# USB_ISOL.net
KiCad netlist of a schematic drawn in Altium Designer
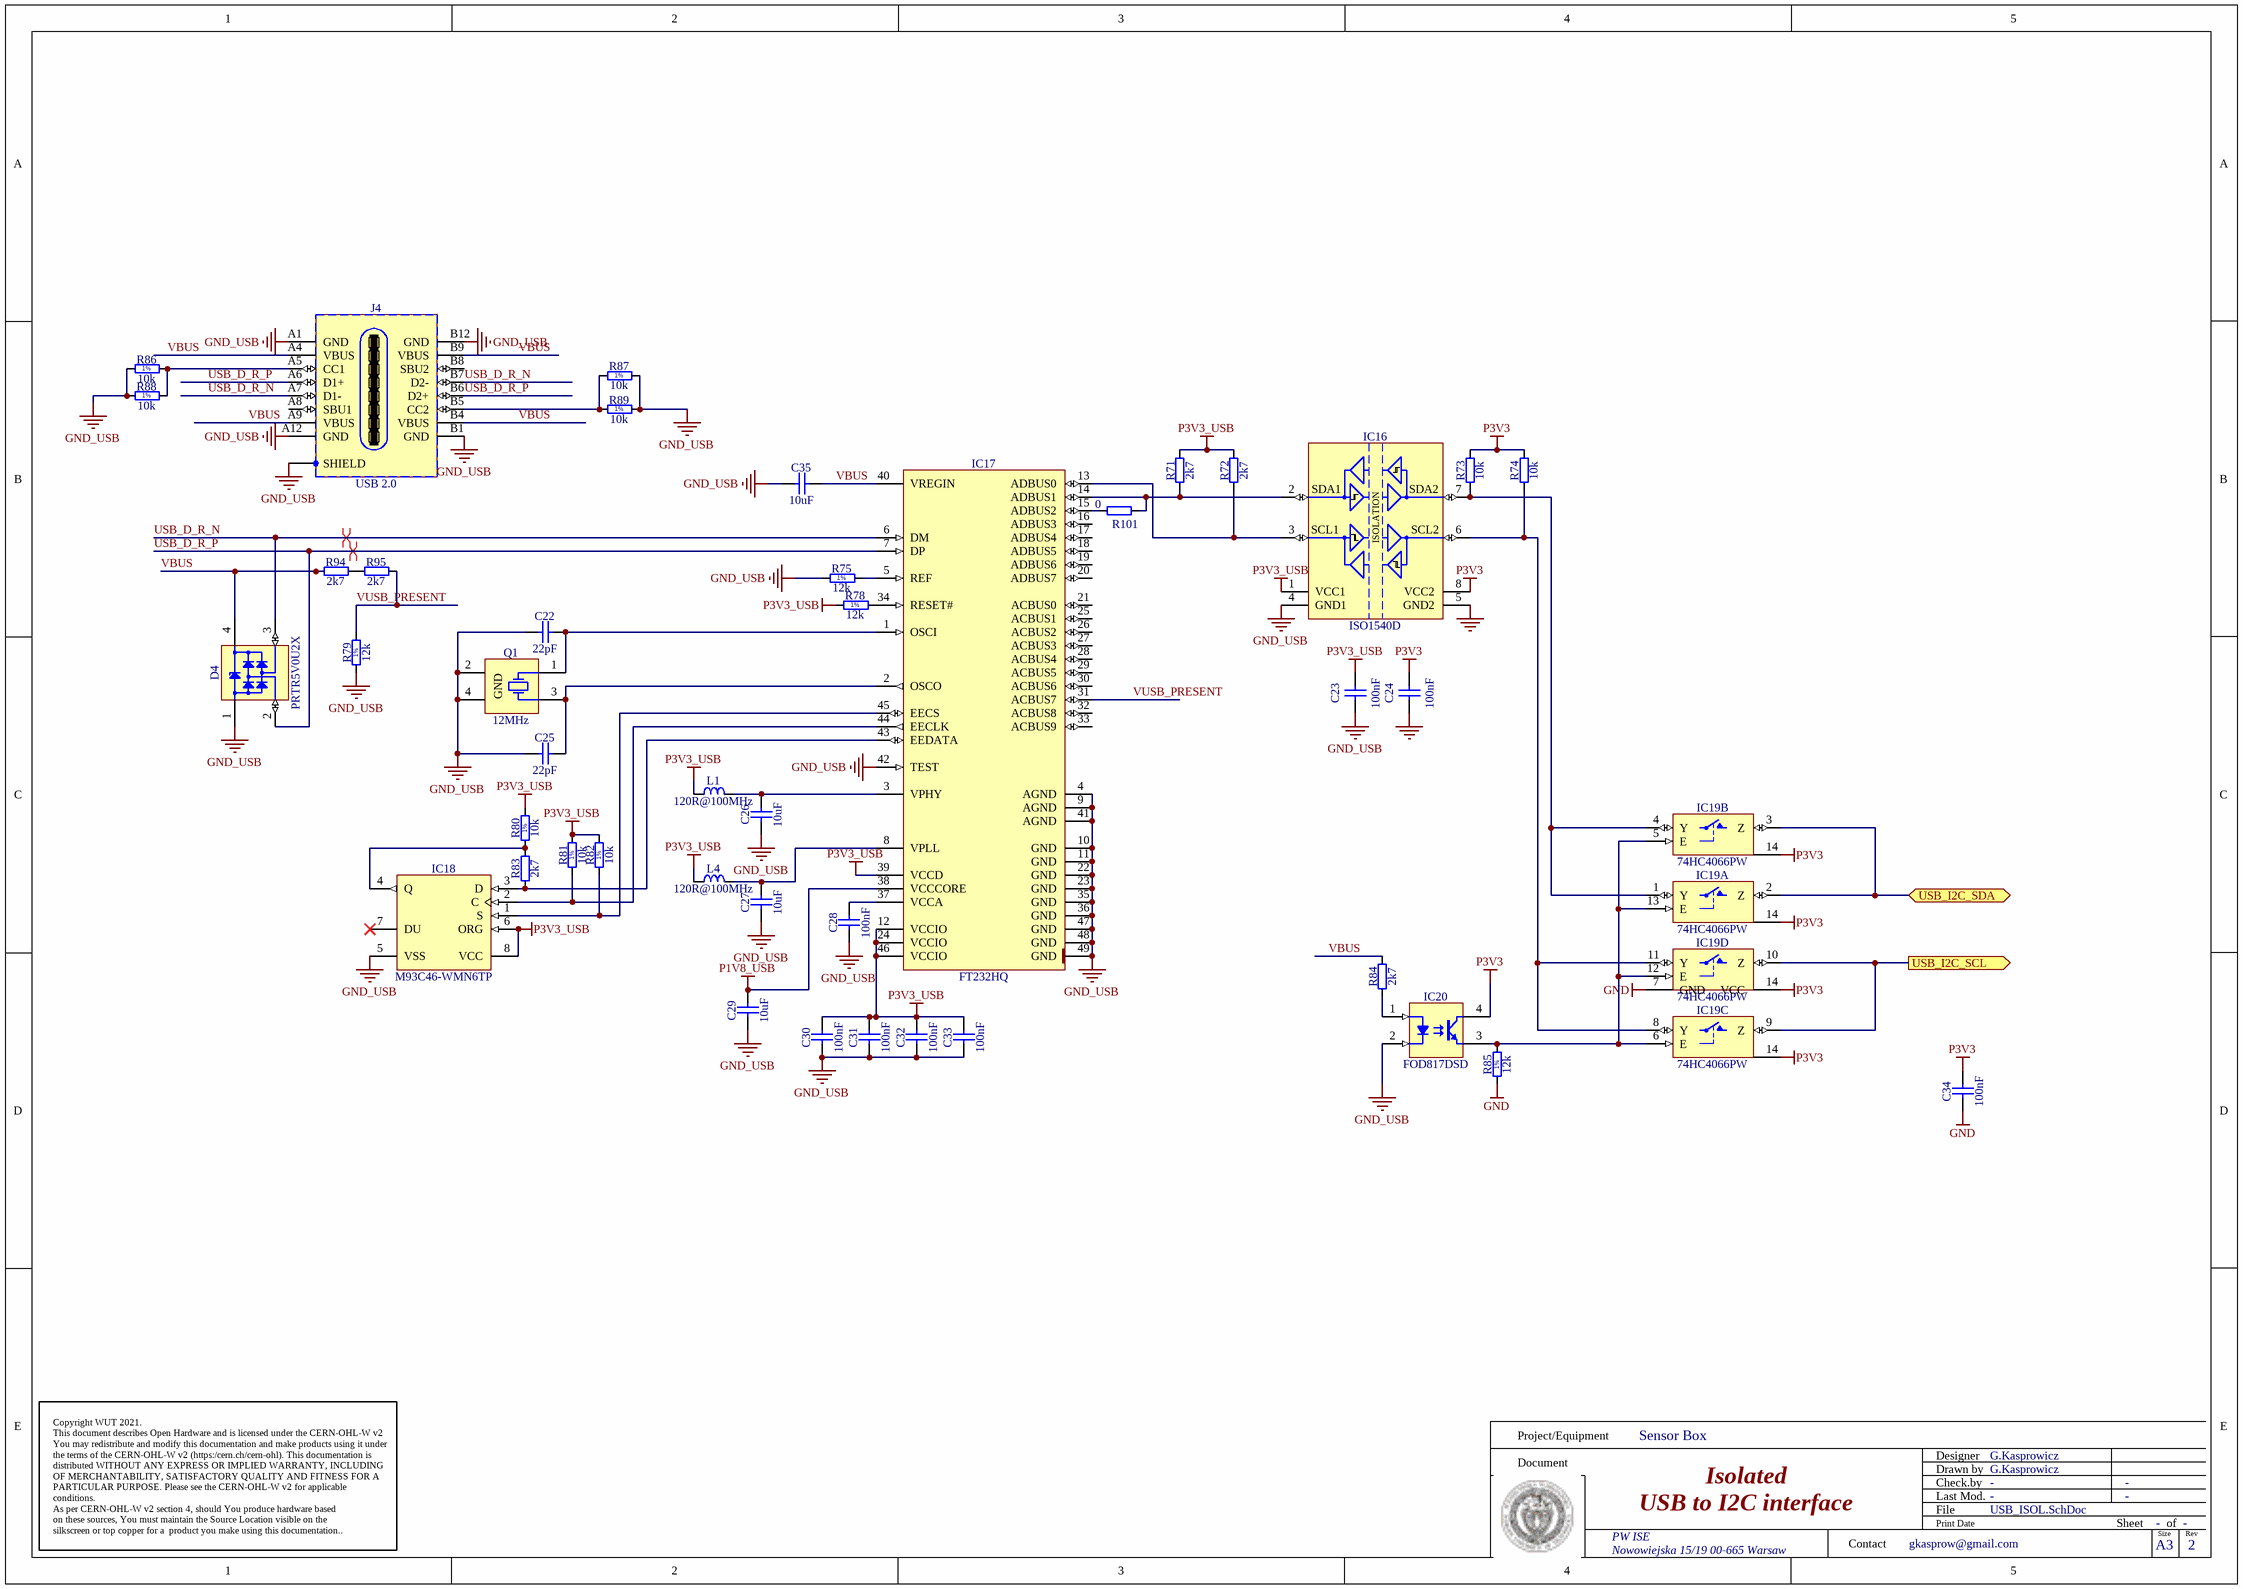
[diagram p0: USB_ISOL.SchDoc]

(export (version "E")
  (design (tool "Eeschema 10.0.6"))
  (components
    (comp (ref "C22")
      (value "22pF")
      (footprint "CAPC1005X55N")
      (description "Non-polarised capacitor")
      (fields
        (field (name "PART NUMBER") "CC0402_22PF_50V_5%_C0G")
        (field (name "VOLTAGE") "50V")
        (field (name "AUTHOR") "CERN DEM JLC")
      )
      (libsource (lib "Capacitors") (part "Capacitor - non polarized"))
    )
    (comp (ref "C23")
      (value "100nF")
      (footprint "CAPC1005X55N")
      (description "Non-polarised capacitor")
      (fields
        (field (name "PART NUMBER") "CC0402_100NF_50V_10%_X7R")
        (field (name "VOLTAGE") "50V")
        (field (name "AUTHOR") "CERN DEM MR")
      )
      (libsource (lib "Capacitors") (part "Capacitor - non polarized"))
    )
    (comp (ref "C24")
      (value "100nF")
      (footprint "CAPC1005X55N")
      (description "Non-polarised capacitor")
      (fields
        (field (name "PART NUMBER") "CC0402_100NF_50V_10%_X7R")
        (field (name "VOLTAGE") "50V")
        (field (name "AUTHOR") "CERN DEM MR")
      )
      (libsource (lib "Capacitors") (part "Capacitor - non polarized"))
    )
    (comp (ref "C25")
      (value "22pF")
      (footprint "CAPC1005X55N")
      (description "Non-polarised capacitor")
      (fields
        (field (name "PART NUMBER") "CC0402_22PF_50V_5%_C0G")
        (field (name "VOLTAGE") "50V")
        (field (name "AUTHOR") "CERN DEM JLC")
      )
      (libsource (lib "Capacitors") (part "Capacitor - non polarized"))
    )
    (comp (ref "C26")
      (value "10uF")
      (footprint "CAPC2012X95N")
      (description "Non-polarised capacitor")
      (fields
        (field (name "PART NUMBER") "CC0805_10UF_25V_10%_X5R")
        (field (name "VOLTAGE") "25V")
        (field (name "AUTHOR") "CERN DEM JLC")
      )
      (libsource (lib "Capacitors") (part "Capacitor - non polarized"))
    )
    (comp (ref "C27")
      (value "10uF")
      (footprint "CAPC2012X95N")
      (description "Non-polarised capacitor")
      (fields
        (field (name "PART NUMBER") "CC0805_10UF_25V_10%_X5R")
        (field (name "VOLTAGE") "25V")
        (field (name "AUTHOR") "CERN DEM JLC")
      )
      (libsource (lib "Capacitors") (part "Capacitor - non polarized"))
    )
    (comp (ref "C28")
      (value "100nF")
      (footprint "CAPC1005X55N")
      (description "Non-polarised capacitor")
      (fields
        (field (name "PART NUMBER") "CC0402_100NF_50V_10%_X7R")
        (field (name "VOLTAGE") "50V")
        (field (name "AUTHOR") "CERN DEM MR")
      )
      (libsource (lib "Capacitors") (part "Capacitor - non polarized"))
    )
    (comp (ref "C29")
      (value "10uF")
      (footprint "CAPC2012X95N")
      (description "Non-polarised capacitor")
      (fields
        (field (name "PART NUMBER") "CC0805_10UF_25V_10%_X5R")
        (field (name "VOLTAGE") "25V")
        (field (name "AUTHOR") "CERN DEM JLC")
      )
      (libsource (lib "Capacitors") (part "Capacitor - non polarized"))
    )
    (comp (ref "C30")
      (value "100nF")
      (footprint "CAPC1005X55N")
      (description "Non-polarised capacitor")
      (fields
        (field (name "PART NUMBER") "CC0402_100NF_50V_10%_X7R")
        (field (name "VOLTAGE") "50V")
        (field (name "AUTHOR") "CERN DEM MR")
      )
      (libsource (lib "Capacitors") (part "Capacitor - non polarized"))
    )
    (comp (ref "C31")
      (value "100nF")
      (footprint "CAPC1005X55N")
      (description "Non-polarised capacitor")
      (fields
        (field (name "PART NUMBER") "CC0402_100NF_50V_10%_X7R")
        (field (name "VOLTAGE") "50V")
        (field (name "AUTHOR") "CERN DEM MR")
      )
      (libsource (lib "Capacitors") (part "Capacitor - non polarized"))
    )
    (comp (ref "C32")
      (value "100nF")
      (footprint "CAPC1005X55N")
      (description "Non-polarised capacitor")
      (fields
        (field (name "PART NUMBER") "CC0402_100NF_50V_10%_X7R")
        (field (name "VOLTAGE") "50V")
        (field (name "AUTHOR") "CERN DEM MR")
      )
      (libsource (lib "Capacitors") (part "Capacitor - non polarized"))
    )
    (comp (ref "C33")
      (value "100nF")
      (footprint "CAPC1005X55N")
      (description "Non-polarised capacitor")
      (fields
        (field (name "PART NUMBER") "CC0402_100NF_50V_10%_X7R")
        (field (name "VOLTAGE") "50V")
        (field (name "AUTHOR") "CERN DEM MR")
      )
      (libsource (lib "Capacitors") (part "Capacitor - non polarized"))
    )
    (comp (ref "C34")
      (value "100nF")
      (footprint "CAPC1005X55N")
      (description "Non-polarised capacitor")
      (fields
        (field (name "PART NUMBER") "CC0402_100NF_50V_10%_X7R")
        (field (name "VOLTAGE") "50V")
        (field (name "AUTHOR") "CERN DEM MR")
      )
      (libsource (lib "Capacitors") (part "Capacitor - non polarized"))
    )
    (comp (ref "C35")
      (value "10uF")
      (footprint "CAPC2012X95N")
      (description "Non-polarised capacitor")
      (fields
        (field (name "PART NUMBER") "CC0805_10UF_25V_10%_X5R")
        (field (name "VOLTAGE") "25V")
        (field (name "AUTHOR") "CERN DEM JLC")
      )
      (libsource (lib "Capacitors") (part "Capacitor - non polarized"))
    )
    (comp (ref "D4")
      (value "PRTR5V0U2X")
      (footprint "SOT190P230X110-4N")
      (description "Ultra Low Capacitance Double Rail-to-Rail ESD Protection Diode")
      (fields
        (field (name "VOLTAGE") "5.5V")
        (field (name "MANUFACTURER") "NXP SEMICONDUCTORS")
        (field (name "AUTHOR") "CERN DEM JLC")
      )
      (libsource (lib "ICs And Semiconductors") (part "PRTR5V0U2X"))
    )
    (comp (ref "IC16")
      (value "ISO1540D")
      (footprint "SOIC127P600X175-8N")
      (description "Low-Power Bi-Directional I2C Isolator")
      (fields (field (name "MANUFACTURER") "TEXAS INSTRUMENTS") (field (name "AUTHOR") "CERN DEM JLC"))
      (libsource (lib "ICs And Semiconductors") (part "ISO1540"))
    )
    (comp (ref "IC17")
      (value "FT232HQ")
      (footprint "QFN50P800X800X90-49N-S625")
      (description "Single channel High Speed USB To Multipurpose UART/FIFO IC")
      (fields
        (field (name "MANUFACTURER") "FUTURE TECHNOLOGY DEVICES INTERNATIONAL (FTDI)")
        (field (name "AUTHOR") "CERN DEM BC")
      )
      (libsource (lib "ICs And Semiconductors") (part "FT232HQ"))
    )
    (comp (ref "IC18")
      (value "M93C46-WMN6TP")
      (footprint "SOIC127P600X175-8N")
      (description "2.5 to 5.5 V, 1Kb (128x8) Serial Microwire Bus EEPROM")
      (fields (field (name "MANUFACTURER") "ST MICROELECTRONICS") (field (name "AUTHOR") "CERN DEM JLC"))
      (libsource (lib "ICs And Semiconductors") (part "M93C46-WMN6TP"))
    )
    (comp (ref "IC19")
      (value "74HC4066PW")
      (footprint "SOP65P640X110-14N")
      (fields (field (name "MANUFACTURER") "NXP SEMICONDUCTORS") (field (name "AUTHOR") "CERN DEM JLC"))
      (libsource (lib "ICs And Semiconductors") (part "4066"))
    )
    (comp (ref "IC20")
      (value "FOD817DSD")
      (footprint "FAIRCHILD_FOD817DSD")
      (description "Single Optocoupler")
      (fields (field (name "MANUFACTURER") "FAIRCHILD SEMICONDUCTOR") (field (name "AUTHOR") "CERN DEM JLC"))
      (libsource (lib "ICs And Semiconductors") (part "Optocoupler Type7"))
    )
    (comp (ref "J4")
      (value "USB 2.0")
      (footprint "GCT_USB4105-GF-A")
      (description "2x8 Pin + 1 Shield  USB Type C Receptacle")
      (fields
        (field (name "PART NUMBER") "GCT_USB4105-GF-A")
        (field (name "MANUFACTURER") "GCT")
        (field (name "AUTHOR") "CERN DEM HF")
      )
      (libsource (lib "Connectors") (part "GCT_USB4105-GF-A"))
    )
    (comp (ref "L1")
      (value "120R@100MHz")
      (footprint "INDC1608X65N")
      (description "Inductor")
      (fields
        (field (name "PART NUMBER") "IND0603_MURATA_BLM18SG121TN1D")
        (field (name "POWER") "3A")
        (field (name "AUTHOR") "CERN DEM JLC")
      )
      (libsource (lib "Inductors & Transformers") (part "Inductor"))
    )
    (comp (ref "L4")
      (value "120R@100MHz")
      (footprint "INDC1608X65N")
      (description "Inductor")
      (fields
        (field (name "PART NUMBER") "IND0603_MURATA_BLM18SG121TN1D")
        (field (name "POWER") "3A")
        (field (name "AUTHOR") "CERN DEM JLC")
      )
      (libsource (lib "Inductors & Transformers") (part "Inductor"))
    )
    (comp (ref "Q1")
      (value "12MHz")
      (footprint "XTAL_TXC_7M")
      (description "Crystal 4 pins 1=XTAL Control 2=GND3=XTAL 4=GND")
      (fields
        (field (name "PART NUMBER") "XTAL_12MHZ_TXC_7M-12.000MAAJ-T")
        (field (name "MANUFACTURER") "TXC CORPORATION")
        (field (name "AUTHOR") "CERN DEM JLC")
      )
      (libsource (lib "ICs And Semiconductors") (part "Quartz Crystal 1X 2GND 3X 4GND"))
    )
    (comp (ref "R71")
      (value "2k7")
      (footprint "RESC1608X55N")
      (description "Resistor - 1%")
      (fields
        (field (name "PART NUMBER") "R0603_2K7_1%_0.1W_100PPM")
        (field (name "POWER") "0.1W")
        (field (name "AUTHOR") "CERN DEM JLC")
      )
      (libsource (lib "") (part "Resistor - 1%_1"))
    )
    (comp (ref "R72")
      (value "2k7")
      (footprint "RESC1608X55N")
      (description "Resistor - 1%")
      (fields
        (field (name "PART NUMBER") "R0603_2K7_1%_0.1W_100PPM")
        (field (name "POWER") "0.1W")
        (field (name "AUTHOR") "CERN DEM JLC")
      )
      (libsource (lib "") (part "Resistor - 1%_1"))
    )
    (comp (ref "R73")
      (value "10k")
      (footprint "RESC1005X40N")
      (description "Resistor - 1%")
      (fields
        (field (name "PART NUMBER") "R0402_10K_1%_0.0625W_100PPM")
        (field (name "POWER") "0.0625W")
        (field (name "AUTHOR") "CERN DEM JLC")
      )
      (libsource (lib "Resistors") (part "Resistor - 1%"))
    )
    (comp (ref "R74")
      (value "10k")
      (footprint "RESC1005X40N")
      (description "Resistor - 1%")
      (fields
        (field (name "PART NUMBER") "R0402_10K_1%_0.0625W_100PPM")
        (field (name "POWER") "0.0625W")
        (field (name "AUTHOR") "CERN DEM JLC")
      )
      (libsource (lib "Resistors") (part "Resistor - 1%"))
    )
    (comp (ref "R75")
      (value "12k")
      (footprint "RESC1005X40N")
      (description "Resistor - 1%")
      (fields
        (field (name "PART NUMBER") "R0402_12K_1%_0.0625W_100PPM")
        (field (name "POWER") "0.0625W")
        (field (name "AUTHOR") "CERN DEM JLC")
      )
      (libsource (lib "Resistors") (part "Resistor - 1%"))
    )
    (comp (ref "R78")
      (value "12k")
      (footprint "RESC1005X40N")
      (description "Resistor - 1%")
      (fields
        (field (name "PART NUMBER") "R0402_12K_1%_0.0625W_100PPM")
        (field (name "POWER") "0.0625W")
        (field (name "AUTHOR") "CERN DEM JLC")
      )
      (libsource (lib "Resistors") (part "Resistor - 1%"))
    )
    (comp (ref "R79")
      (value "12k")
      (footprint "RESC1005X40N")
      (description "Resistor - 1%")
      (fields
        (field (name "PART NUMBER") "R0402_12K_1%_0.0625W_100PPM")
        (field (name "POWER") "0.0625W")
        (field (name "AUTHOR") "CERN DEM JLC")
      )
      (libsource (lib "Resistors") (part "Resistor - 1%"))
    )
    (comp (ref "R80")
      (value "10k")
      (footprint "RESC1005X40N")
      (description "Resistor - 1%")
      (fields
        (field (name "PART NUMBER") "R0402_10K_1%_0.0625W_100PPM")
        (field (name "POWER") "0.0625W")
        (field (name "AUTHOR") "CERN DEM JLC")
      )
      (libsource (lib "Resistors") (part "Resistor - 1%"))
    )
    (comp (ref "R81")
      (value "10k")
      (footprint "RESC1005X40N")
      (description "Resistor - 1%")
      (fields
        (field (name "PART NUMBER") "R0402_10K_1%_0.0625W_100PPM")
        (field (name "POWER") "0.0625W")
        (field (name "AUTHOR") "CERN DEM JLC")
      )
      (libsource (lib "Resistors") (part "Resistor - 1%"))
    )
    (comp (ref "R82")
      (value "10k")
      (footprint "RESC1005X40N")
      (description "Resistor - 1%")
      (fields
        (field (name "PART NUMBER") "R0402_10K_1%_0.0625W_100PPM")
        (field (name "POWER") "0.0625W")
        (field (name "AUTHOR") "CERN DEM JLC")
      )
      (libsource (lib "Resistors") (part "Resistor - 1%"))
    )
    (comp (ref "R83")
      (value "2k7")
      (footprint "RESC1608X55N")
      (description "Resistor - 1%")
      (fields
        (field (name "PART NUMBER") "R0603_2K7_1%_0.1W_100PPM")
        (field (name "POWER") "0.1W")
        (field (name "AUTHOR") "CERN DEM JLC")
      )
      (libsource (lib "") (part "Resistor - 1%_1"))
    )
    (comp (ref "R84")
      (value "2k7")
      (footprint "RESC1608X55N")
      (description "Resistor - 1%")
      (fields
        (field (name "PART NUMBER") "R0603_2K7_1%_0.1W_100PPM")
        (field (name "POWER") "0.1W")
        (field (name "AUTHOR") "CERN DEM JLC")
      )
      (libsource (lib "") (part "Resistor - 1%_1"))
    )
    (comp (ref "R85")
      (value "12k")
      (footprint "RESC1005X40N")
      (description "Resistor - 1%")
      (fields
        (field (name "PART NUMBER") "R0402_12K_1%_0.0625W_100PPM")
        (field (name "POWER") "0.0625W")
        (field (name "AUTHOR") "CERN DEM JLC")
      )
      (libsource (lib "Resistors") (part "Resistor - 1%"))
    )
    (comp (ref "R86")
      (value "10k")
      (footprint "RESC1005X40N")
      (description "Resistor - 1%")
      (fields
        (field (name "PART NUMBER") "R0402_10K_1%_0.0625W_100PPM")
        (field (name "POWER") "0.0625W")
        (field (name "AUTHOR") "CERN DEM JLC")
      )
      (libsource (lib "Resistors") (part "Resistor - 1%"))
    )
    (comp (ref "R87")
      (value "10k")
      (footprint "RESC1005X40N")
      (description "Resistor - 1%")
      (fields
        (field (name "PART NUMBER") "R0402_10K_1%_0.0625W_100PPM")
        (field (name "POWER") "0.0625W")
        (field (name "AUTHOR") "CERN DEM JLC")
      )
      (libsource (lib "Resistors") (part "Resistor - 1%"))
    )
    (comp (ref "R88")
      (value "10k")
      (footprint "RESC1005X40N")
      (description "Resistor - 1%")
      (fields
        (field (name "PART NUMBER") "R0402_10K_1%_0.0625W_100PPM")
        (field (name "POWER") "0.0625W")
        (field (name "AUTHOR") "CERN DEM JLC")
      )
      (libsource (lib "Resistors") (part "Resistor - 1%"))
    )
    (comp (ref "R89")
      (value "10k")
      (footprint "RESC1005X40N")
      (description "Resistor - 1%")
      (fields
        (field (name "PART NUMBER") "R0402_10K_1%_0.0625W_100PPM")
        (field (name "POWER") "0.0625W")
        (field (name "AUTHOR") "CERN DEM JLC")
      )
      (libsource (lib "Resistors") (part "Resistor - 1%"))
    )
    (comp (ref "R94")
      (value "2k7")
      (footprint "RESC1608X55N")
      (description "Resistor - 1%")
      (fields
        (field (name "PART NUMBER") "R0603_2K7_1%_0.1W_100PPM")
        (field (name "POWER") "0.1W")
        (field (name "AUTHOR") "CERN DEM JLC")
      )
      (libsource (lib "") (part "Resistor - 1%_1"))
    )
    (comp (ref "R95")
      (value "2k7")
      (footprint "RESC1608X55N")
      (description "Resistor - 1%")
      (fields
        (field (name "PART NUMBER") "R0603_2K7_1%_0.1W_100PPM")
        (field (name "POWER") "0.1W")
        (field (name "AUTHOR") "CERN DEM JLC")
      )
      (libsource (lib "") (part "Resistor - 1%_1"))
    )
    (comp (ref "R101")
      (value "0")
      (footprint "RESC1005X40N")
      (description "Resistor")
      (fields
        (field (name "PART NUMBER") "R0402_0R_JUMPER")
        (field (name "MANUFACTURER") "GENERIC")
        (field (name "AUTHOR") "CERN DEM JLC")
      )
      (libsource (lib "Resistors") (part "Resistor"))
    )
  )
  (nets
    (net (code "1") (name "/USB_D_R_N") (class "Default")
      (node (ref "D4") (pin "3") (pinfunction "I/O2_3") (pintype "bidirectional"))
      (node (ref "IC17") (pin "6") (pinfunction "DM_6") (pintype "input"))
      (node (ref "J4") (pin "A7") (pinfunction "D1-_A7") (pintype "bidirectional"))
      (node (ref "J4") (pin "B7") (pinfunction "D2-_B7") (pintype "bidirectional"))
    )
    (net (code "2") (name "/USB_D_R_P") (class "Default")
      (node (ref "D4") (pin "2") (pinfunction "I/O1_2") (pintype "bidirectional"))
      (node (ref "IC17") (pin "7") (pinfunction "DP_7") (pintype "input"))
      (node (ref "J4") (pin "A6") (pinfunction "D1+_A6") (pintype "bidirectional"))
      (node (ref "J4") (pin "B6") (pinfunction "D2+_B6") (pintype "bidirectional"))
    )
    (net (code "3") (name "/USB_I2C_SCL") (class "Default")
      (node (ref "IC19") (pin "10") (pinfunction "Z_10") (pintype "bidirectional"))
      (node (ref "IC19") (pin "9") (pinfunction "Z_9") (pintype "bidirectional"))
    )
    (net (code "4") (name "/USB_I2C_SDA") (class "Default")
      (node (ref "IC19") (pin "2") (pinfunction "Z_2") (pintype "bidirectional"))
      (node (ref "IC19") (pin "3") (pinfunction "Z_3") (pintype "bidirectional"))
    )
    (net (code "5") (name "/VBUS") (class "Default")
      (node (ref "C35") (pin "2") (pinfunction "2_2") (pintype "passive"))
      (node (ref "D4") (pin "4") (pinfunction "VCC_4") (pintype "power_in"))
      (node (ref "IC17") (pin "40") (pinfunction "VREGIN_40") (pintype "power_in"))
      (node (ref "J4") (pin "A4") (pinfunction "VBUS_A4") (pintype "power_in"))
      (node (ref "J4") (pin "A9") (pinfunction "VBUS_A9") (pintype "power_in"))
      (node (ref "J4") (pin "B4") (pinfunction "VBUS_B4") (pintype "power_in"))
      (node (ref "J4") (pin "B9") (pinfunction "VBUS_B9") (pintype "power_in"))
      (node (ref "R84") (pin "1") (pinfunction "1_1") (pintype "passive"))
      (node (ref "R94") (pin "1") (pinfunction "1_1") (pintype "passive"))
    )
    (net (code "6") (name "/VUSB_PRESENT") (class "Default")
      (node (ref "IC17") (pin "31") (pinfunction "ACBUS7_31") (pintype "bidirectional"))
      (node (ref "R79") (pin "2") (pinfunction "2_2") (pintype "passive"))
      (node (ref "R95") (pin "2") (pinfunction "2_2") (pintype "passive"))
    )
    (net (code "7") (name "GND") (class "Default")
      (node (ref "C24") (pin "1") (pinfunction "1_1") (pintype "passive"))
      (node (ref "C34") (pin "1") (pinfunction "1_1") (pintype "passive"))
      (node (ref "IC16") (pin "5") (pinfunction "GND2_5") (pintype "power_in"))
      (node (ref "IC19") (pin "7") (pinfunction "GND_7") (pintype "power_in"))
      (node (ref "R85") (pin "1") (pinfunction "1_1") (pintype "passive"))
    )
    (net (code "8") (name "GND_USB") (class "Default")
      (node (ref "C22") (pin "1") (pinfunction "1_1") (pintype "passive"))
      (node (ref "C23") (pin "1") (pinfunction "1_1") (pintype "passive"))
      (node (ref "C25") (pin "1") (pinfunction "1_1") (pintype "passive"))
      (node (ref "C26") (pin "1") (pinfunction "1_1") (pintype "passive"))
      (node (ref "C27") (pin "1") (pinfunction "1_1") (pintype "passive"))
      (node (ref "C28") (pin "1") (pinfunction "1_1") (pintype "passive"))
      (node (ref "C29") (pin "1") (pinfunction "1_1") (pintype "passive"))
      (node (ref "C30") (pin "1") (pinfunction "1_1") (pintype "passive"))
      (node (ref "C31") (pin "1") (pinfunction "1_1") (pintype "passive"))
      (node (ref "C32") (pin "1") (pinfunction "1_1") (pintype "passive"))
      (node (ref "C33") (pin "1") (pinfunction "1_1") (pintype "passive"))
      (node (ref "C35") (pin "1") (pinfunction "1_1") (pintype "passive"))
      (node (ref "D4") (pin "1") (pinfunction "GND_1") (pintype "power_in"))
      (node (ref "IC16") (pin "4") (pinfunction "GND1_4") (pintype "power_in"))
      (node (ref "IC17") (pin "10") (pinfunction "GND_10") (pintype "power_in"))
      (node (ref "IC17") (pin "11") (pinfunction "GND_11") (pintype "power_in"))
      (node (ref "IC17") (pin "22") (pinfunction "GND_22") (pintype "power_in"))
      (node (ref "IC17") (pin "23") (pinfunction "GND_23") (pintype "power_in"))
      (node (ref "IC17") (pin "35") (pinfunction "GND_35") (pintype "power_in"))
      (node (ref "IC17") (pin "36") (pinfunction "GND_36") (pintype "power_in"))
      (node (ref "IC17") (pin "4") (pinfunction "AGND_4") (pintype "power_in"))
      (node (ref "IC17") (pin "41") (pinfunction "AGND_41") (pintype "power_in"))
      (node (ref "IC17") (pin "42") (pinfunction "TEST_42") (pintype "input"))
      (node (ref "IC17") (pin "47") (pinfunction "GND_47") (pintype "power_in"))
      (node (ref "IC17") (pin "48") (pinfunction "GND_48") (pintype "power_in"))
      (node (ref "IC17") (pin "49") (pinfunction "GND_49") (pintype "power_in"))
      (node (ref "IC17") (pin "9") (pinfunction "AGND_9") (pintype "power_in"))
      (node (ref "IC18") (pin "5") (pinfunction "VSS_5") (pintype "power_in"))
      (node (ref "IC20") (pin "2") (pinfunction "C_2") (pintype "input"))
      (node (ref "J4") (pin "A1") (pinfunction "GND_A1") (pintype "power_in"))
      (node (ref "J4") (pin "A12") (pinfunction "GND_A12") (pintype "power_in"))
      (node (ref "J4") (pin "B1") (pinfunction "GND_B1") (pintype "power_in"))
      (node (ref "J4") (pin "B12") (pinfunction "GND_B12") (pintype "power_in"))
      (node (ref "J4") (pin "SHIELD") (pinfunction "SHIELD_SHIELD") (pintype "power_in"))
      (node (ref "Q1") (pin "2") (pinfunction "GND_2") (pintype "power_in"))
      (node (ref "Q1") (pin "4") (pinfunction "GND_4") (pintype "power_in"))
      (node (ref "R75") (pin "1") (pinfunction "1_1") (pintype "passive"))
      (node (ref "R79") (pin "1") (pinfunction "1_1") (pintype "passive"))
      (node (ref "R86") (pin "1") (pinfunction "1_1") (pintype "passive"))
      (node (ref "R87") (pin "2") (pinfunction "2_2") (pintype "passive"))
      (node (ref "R88") (pin "1") (pinfunction "1_1") (pintype "passive"))
      (node (ref "R89") (pin "2") (pinfunction "2_2") (pintype "passive"))
    )
    (net (code "9") (name "Net-(IC16-SCL1)") (class "Default")
      (node (ref "IC16") (pin "3") (pinfunction "SCL1_3") (pintype "bidirectional"))
      (node (ref "IC17") (pin "13") (pinfunction "ADBUS0_13") (pintype "bidirectional"))
      (node (ref "R72") (pin "1") (pinfunction "1_1") (pintype "passive"))
    )
    (net (code "10") (name "Net-(IC16-SCL2)") (class "Default")
      (node (ref "IC16") (pin "6") (pinfunction "SCL2_6") (pintype "bidirectional"))
      (node (ref "IC19") (pin "11") (pinfunction "Y_11") (pintype "bidirectional"))
      (node (ref "IC19") (pin "8") (pinfunction "Y_8") (pintype "bidirectional"))
      (node (ref "R74") (pin "1") (pinfunction "1_1") (pintype "passive"))
    )
    (net (code "11") (name "Net-(IC16-SDA1)") (class "Default")
      (node (ref "IC16") (pin "2") (pinfunction "SDA1_2") (pintype "bidirectional"))
      (node (ref "IC17") (pin "14") (pinfunction "ADBUS1_14") (pintype "bidirectional"))
      (node (ref "R101") (pin "2") (pinfunction "2_2") (pintype "passive"))
      (node (ref "R71") (pin "1") (pinfunction "1_1") (pintype "passive"))
    )
    (net (code "12") (name "Net-(IC16-SDA2)") (class "Default")
      (node (ref "IC16") (pin "7") (pinfunction "SDA2_7") (pintype "bidirectional"))
      (node (ref "IC19") (pin "1") (pinfunction "Y_1") (pintype "bidirectional"))
      (node (ref "IC19") (pin "4") (pinfunction "Y_4") (pintype "bidirectional"))
      (node (ref "R73") (pin "1") (pinfunction "1_1") (pintype "passive"))
    )
    (net (code "13") (name "Net-(IC17-ADBUS2)") (class "Default")
      (node (ref "IC17") (pin "15") (pinfunction "ADBUS2_15") (pintype "bidirectional"))
      (node (ref "R101") (pin "1") (pinfunction "1_1") (pintype "passive"))
    )
    (net (code "14") (name "Net-(IC17-EECLK)") (class "Default")
      (node (ref "IC17") (pin "44") (pinfunction "EECLK_44") (pintype "output"))
      (node (ref "IC18") (pin "2") (pinfunction "C_2") (pintype "input"))
      (node (ref "R81") (pin "1") (pinfunction "1_1") (pintype "passive"))
    )
    (net (code "15") (name "Net-(IC17-EECS)") (class "Default")
      (node (ref "IC17") (pin "45") (pinfunction "EECS_45") (pintype "bidirectional"))
      (node (ref "IC18") (pin "1") (pinfunction "S_1") (pintype "input"))
      (node (ref "R82") (pin "1") (pinfunction "1_1") (pintype "passive"))
    )
    (net (code "16") (name "Net-(IC17-EEDATA)") (class "Default")
      (node (ref "IC17") (pin "43") (pinfunction "EEDATA_43") (pintype "bidirectional"))
      (node (ref "IC18") (pin "3") (pinfunction "D_3") (pintype "input"))
      (node (ref "R83") (pin "2") (pinfunction "2_2") (pintype "passive"))
    )
    (net (code "17") (name "Net-(IC17-OSCI)") (class "Default")
      (node (ref "C22") (pin "2") (pinfunction "2_2") (pintype "passive"))
      (node (ref "IC17") (pin "1") (pinfunction "OSCI_1") (pintype "input"))
      (node (ref "Q1") (pin "1") (pinfunction "X_1") (pintype "passive"))
    )
    (net (code "18") (name "Net-(IC17-OSCO)") (class "Default")
      (node (ref "C25") (pin "2") (pinfunction "2_2") (pintype "passive"))
      (node (ref "IC17") (pin "2") (pinfunction "OSCO_2") (pintype "output"))
      (node (ref "Q1") (pin "3") (pinfunction "X_3") (pintype "passive"))
    )
    (net (code "19") (name "Net-(IC17-REF)") (class "Default")
      (node (ref "IC17") (pin "5") (pinfunction "REF_5") (pintype "input"))
      (node (ref "R75") (pin "2") (pinfunction "2_2") (pintype "passive"))
    )
    (net (code "20") (name "Net-(IC17-RESET#)") (class "Default")
      (node (ref "IC17") (pin "34") (pinfunction "RESET#_34") (pintype "input"))
      (node (ref "R78") (pin "2") (pinfunction "2_2") (pintype "passive"))
    )
    (net (code "21") (name "Net-(IC17-VCCA)") (class "Default")
      (node (ref "C28") (pin "2") (pinfunction "2_2") (pintype "passive"))
      (node (ref "IC17") (pin "37") (pinfunction "VCCA_37") (pintype "power_in"))
    )
    (net (code "22") (name "Net-(IC17-VPHY)") (class "Default")
      (node (ref "C26") (pin "2") (pinfunction "2_2") (pintype "passive"))
      (node (ref "IC17") (pin "3") (pinfunction "VPHY_3") (pintype "power_in"))
      (node (ref "L1") (pin "2") (pinfunction "2_2") (pintype "passive"))
    )
    (net (code "23") (name "Net-(IC17-VPLL)") (class "Default")
      (node (ref "C27") (pin "2") (pinfunction "2_2") (pintype "passive"))
      (node (ref "IC17") (pin "8") (pinfunction "VPLL_8") (pintype "power_in"))
      (node (ref "L4") (pin "2") (pinfunction "2_2") (pintype "passive"))
    )
    (net (code "24") (name "Net-(IC18-Q)") (class "Default")
      (node (ref "IC18") (pin "4") (pinfunction "Q_4") (pintype "output"))
      (node (ref "R80") (pin "1") (pinfunction "1_1") (pintype "passive"))
      (node (ref "R83") (pin "1") (pinfunction "1_1") (pintype "passive"))
    )
    (net (code "25") (name "Net-(IC19A-E)") (class "Default")
      (node (ref "IC19") (pin "12") (pinfunction "E_12") (pintype "input"))
      (node (ref "IC19") (pin "13") (pinfunction "E_13") (pintype "input"))
      (node (ref "IC19") (pin "5") (pinfunction "E_5") (pintype "input"))
      (node (ref "IC19") (pin "6") (pinfunction "E_6") (pintype "input"))
      (node (ref "IC20") (pin "3") (pinfunction "E_3") (pintype "open_emitter"))
      (node (ref "R85") (pin "2") (pinfunction "2_2") (pintype "passive"))
    )
    (net (code "26") (name "Net-(IC20-A)") (class "Default")
      (node (ref "IC20") (pin "1") (pinfunction "A_1") (pintype "input"))
      (node (ref "R84") (pin "2") (pinfunction "2_2") (pintype "passive"))
    )
    (net (code "27") (name "Net-(J4-CC1)") (class "Default")
      (node (ref "J4") (pin "A5") (pinfunction "CC1_A5") (pintype "bidirectional"))
      (node (ref "R86") (pin "2") (pinfunction "2_2") (pintype "passive"))
      (node (ref "R88") (pin "2") (pinfunction "2_2") (pintype "passive"))
    )
    (net (code "28") (name "Net-(J4-CC2)") (class "Default")
      (node (ref "J4") (pin "B5") (pinfunction "CC2_B5") (pintype "bidirectional"))
      (node (ref "R87") (pin "1") (pinfunction "1_1") (pintype "passive"))
      (node (ref "R89") (pin "1") (pinfunction "1_1") (pintype "passive"))
    )
    (net (code "29") (name "Net-(R94-Pad2)") (class "Default")
      (node (ref "R94") (pin "2") (pinfunction "2_2") (pintype "passive"))
      (node (ref "R95") (pin "1") (pinfunction "1_1") (pintype "passive"))
    )
    (net (code "30") (name "P1V8_USB") (class "Default")
      (node (ref "C29") (pin "2") (pinfunction "2_2") (pintype "passive"))
      (node (ref "IC17") (pin "38") (pinfunction "VCCCORE_38") (pintype "power_in"))
    )
    (net (code "31") (name "P3V3") (class "Default")
      (node (ref "C24") (pin "2") (pinfunction "2_2") (pintype "passive"))
      (node (ref "C34") (pin "2") (pinfunction "2_2") (pintype "passive"))
      (node (ref "IC16") (pin "8") (pinfunction "VCC2_8") (pintype "power_in"))
      (node (ref "IC19") (pin "14") (pinfunction "VCC_14") (pintype "power_in"))
      (node (ref "IC20") (pin "4") (pinfunction "C_4") (pintype "open_collector"))
      (node (ref "R73") (pin "2") (pinfunction "2_2") (pintype "passive"))
      (node (ref "R74") (pin "2") (pinfunction "2_2") (pintype "passive"))
    )
    (net (code "32") (name "P3V3_USB") (class "Default")
      (node (ref "C23") (pin "2") (pinfunction "2_2") (pintype "passive"))
      (node (ref "C30") (pin "2") (pinfunction "2_2") (pintype "passive"))
      (node (ref "C31") (pin "2") (pinfunction "2_2") (pintype "passive"))
      (node (ref "C32") (pin "2") (pinfunction "2_2") (pintype "passive"))
      (node (ref "C33") (pin "2") (pinfunction "2_2") (pintype "passive"))
      (node (ref "IC16") (pin "1") (pinfunction "VCC1_1") (pintype "power_in"))
      (node (ref "IC17") (pin "12") (pinfunction "VCCIO_12") (pintype "power_in"))
      (node (ref "IC17") (pin "24") (pinfunction "VCCIO_24") (pintype "power_in"))
      (node (ref "IC17") (pin "39") (pinfunction "VCCD_39") (pintype "power_in"))
      (node (ref "IC17") (pin "46") (pinfunction "VCCIO_46") (pintype "power_in"))
      (node (ref "IC18") (pin "6") (pinfunction "ORG_6") (pintype "input"))
      (node (ref "IC18") (pin "8") (pinfunction "VCC_8") (pintype "power_in"))
      (node (ref "L1") (pin "1") (pinfunction "1_1") (pintype "passive"))
      (node (ref "L4") (pin "1") (pinfunction "1_1") (pintype "passive"))
      (node (ref "R71") (pin "2") (pinfunction "2_2") (pintype "passive"))
      (node (ref "R72") (pin "2") (pinfunction "2_2") (pintype "passive"))
      (node (ref "R78") (pin "1") (pinfunction "1_1") (pintype "passive"))
      (node (ref "R80") (pin "2") (pinfunction "2_2") (pintype "passive"))
      (node (ref "R81") (pin "2") (pinfunction "2_2") (pintype "passive"))
      (node (ref "R82") (pin "2") (pinfunction "2_2") (pintype "passive"))
    )
    (net (code "33") (name "unconnected-(IC17-ACBUS0-Pad21)") (class "Default")
      (node (ref "IC17") (pin "21") (pinfunction "ACBUS0_21") (pintype "bidirectional"))
    )
    (net (code "34") (name "unconnected-(IC17-ACBUS1-Pad25)") (class "Default")
      (node (ref "IC17") (pin "25") (pinfunction "ACBUS1_25") (pintype "bidirectional"))
    )
    (net (code "35") (name "unconnected-(IC17-ACBUS2-Pad26)") (class "Default")
      (node (ref "IC17") (pin "26") (pinfunction "ACBUS2_26") (pintype "bidirectional"))
    )
    (net (code "36") (name "unconnected-(IC17-ACBUS3-Pad27)") (class "Default")
      (node (ref "IC17") (pin "27") (pinfunction "ACBUS3_27") (pintype "bidirectional"))
    )
    (net (code "37") (name "unconnected-(IC17-ACBUS4-Pad28)") (class "Default")
      (node (ref "IC17") (pin "28") (pinfunction "ACBUS4_28") (pintype "bidirectional"))
    )
    (net (code "38") (name "unconnected-(IC17-ACBUS5-Pad29)") (class "Default")
      (node (ref "IC17") (pin "29") (pinfunction "ACBUS5_29") (pintype "bidirectional"))
    )
    (net (code "39") (name "unconnected-(IC17-ACBUS6-Pad30)") (class "Default")
      (node (ref "IC17") (pin "30") (pinfunction "ACBUS6_30") (pintype "bidirectional"))
    )
    (net (code "40") (name "unconnected-(IC17-ACBUS8-Pad32)") (class "Default")
      (node (ref "IC17") (pin "32") (pinfunction "ACBUS8_32") (pintype "bidirectional"))
    )
    (net (code "41") (name "unconnected-(IC17-ACBUS9-Pad33)") (class "Default")
      (node (ref "IC17") (pin "33") (pinfunction "ACBUS9_33") (pintype "bidirectional"))
    )
    (net (code "42") (name "unconnected-(IC17-ADBUS3-Pad16)") (class "Default")
      (node (ref "IC17") (pin "16") (pinfunction "ADBUS3_16") (pintype "bidirectional"))
    )
    (net (code "43") (name "unconnected-(IC17-ADBUS4-Pad17)") (class "Default")
      (node (ref "IC17") (pin "17") (pinfunction "ADBUS4_17") (pintype "bidirectional"))
    )
    (net (code "44") (name "unconnected-(IC17-ADBUS5-Pad18)") (class "Default")
      (node (ref "IC17") (pin "18") (pinfunction "ADBUS5_18") (pintype "bidirectional"))
    )
    (net (code "45") (name "unconnected-(IC17-ADBUS6-Pad19)") (class "Default")
      (node (ref "IC17") (pin "19") (pinfunction "ADBUS6_19") (pintype "bidirectional"))
    )
    (net (code "46") (name "unconnected-(IC17-ADBUS7-Pad20)") (class "Default")
      (node (ref "IC17") (pin "20") (pinfunction "ADBUS7_20") (pintype "bidirectional"))
    )
    (net (code "47") (name "unconnected-(IC18-DU-Pad7)") (class "Default")
      (node (ref "IC18") (pin "7") (pinfunction "DU_7") (pintype "passive+no_connect"))
    )
    (net (code "48") (name "unconnected-(J4-SBU1-PadA8)") (class "Default")
      (node (ref "J4") (pin "A8") (pinfunction "SBU1_A8") (pintype "bidirectional"))
    )
    (net (code "49") (name "unconnected-(J4-SBU2-PadB8)") (class "Default")
      (node (ref "J4") (pin "B8") (pinfunction "SBU2_B8") (pintype "bidirectional"))
    )
  )
)
